# SDP_1.net
KiCad netlist of a schematic drawn in Altium Designer
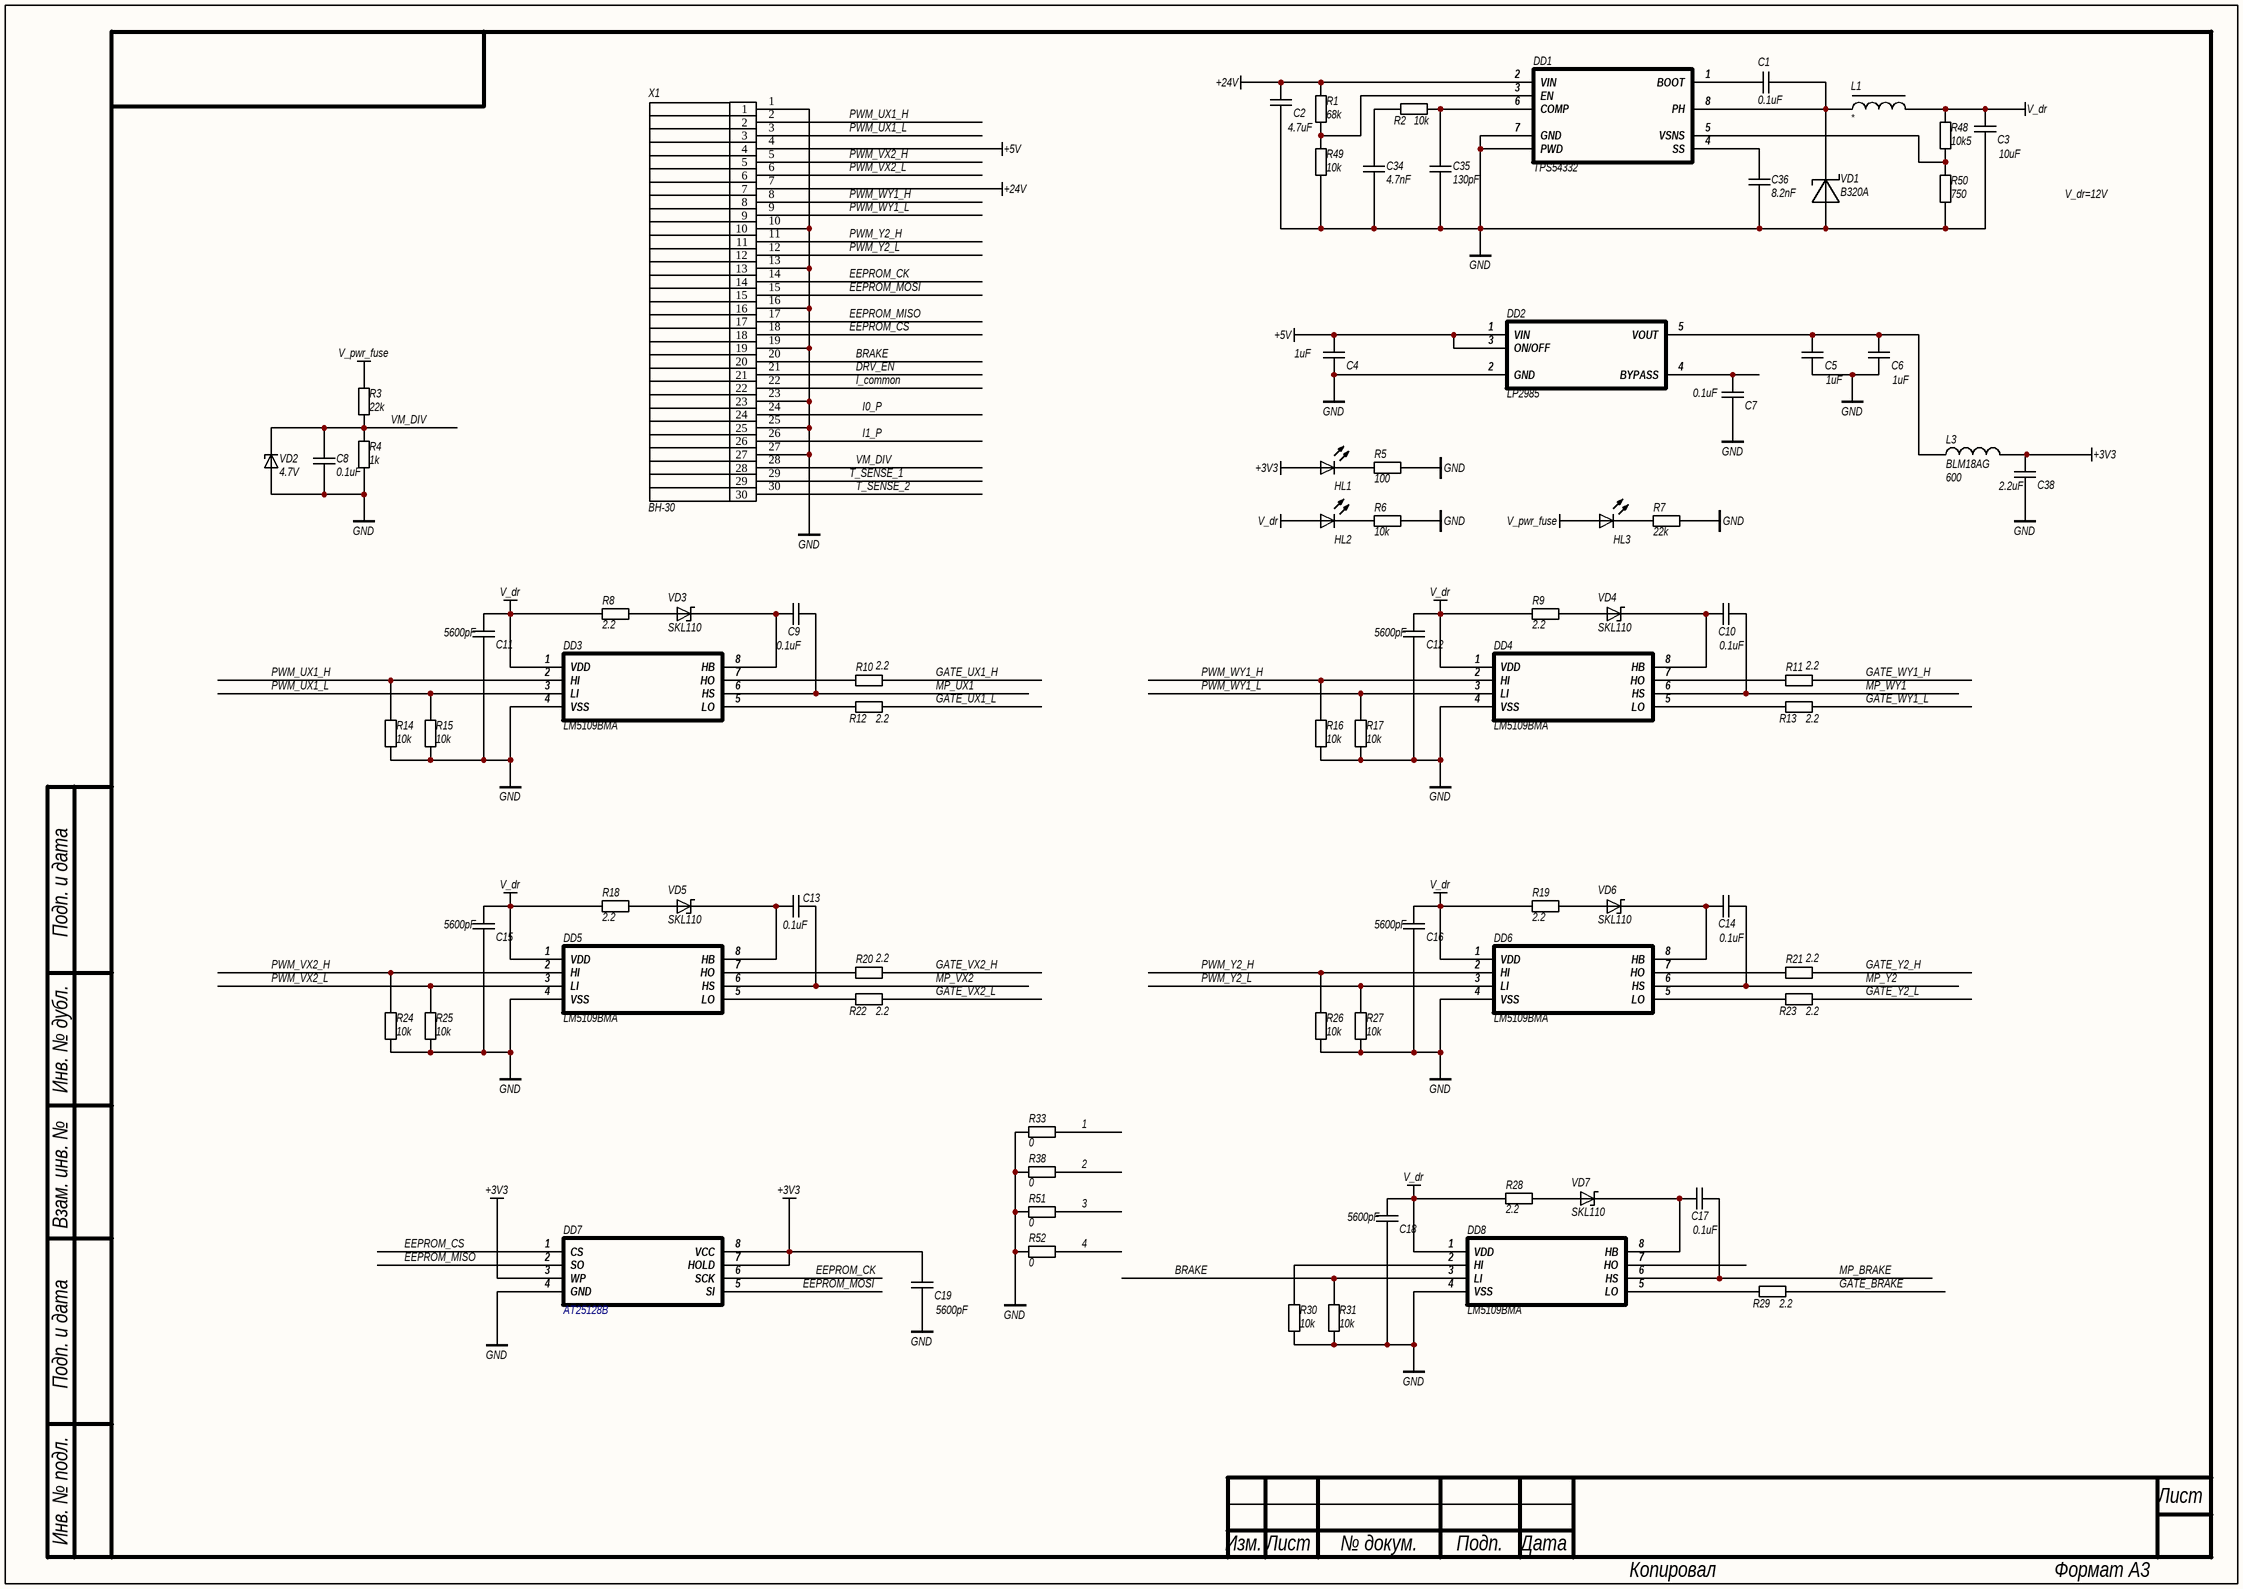
[diagram p0: SDP_1.SchDoc]

(export (version "E")
  (design (tool "Eeschema 10.0.6"))
  (components
    (comp (ref "C1")
      (value "0.1uF")
      (footprint "C0603")
      (description "SMD Capacitor")
      (fields (field (name "MANUFACTURER") "Murata") (field (name "TOLERANCE") "10%"))
      (libsource (lib "VKA") (part "CAP"))
    )
    (comp (ref "C2")
      (value "4.7uF")
      (footprint "C1210")
      (description "SMD Capacitor")
      (fields (field (name "MANUFACTURER") "Murata") (field (name "TOLERANCE") "10%"))
      (libsource (lib "VKA") (part "CAP"))
    )
    (comp (ref "C3")
      (value "10uF")
      (footprint "C1210")
      (description "SMD Capacitor")
      (fields (field (name "MANUFACTURER") "Murata") (field (name "TOLERANCE") "10%"))
      (libsource (lib "VKA") (part "CAP"))
    )
    (comp (ref "C4")
      (value "1uF")
      (footprint "C0603")
      (description "SMD Capacitor")
      (fields (field (name "MANUFACTURER") "Murata") (field (name "TOLERANCE") "10%"))
      (libsource (lib "VKA") (part "CAP"))
    )
    (comp (ref "C5")
      (value "1uF")
      (footprint "C0603")
      (description "SMD Capacitor")
      (fields (field (name "MANUFACTURER") "Murata") (field (name "TOLERANCE") "10%"))
      (libsource (lib "VKA") (part "CAP"))
    )
    (comp (ref "C6")
      (value "1uF")
      (footprint "C0603")
      (description "SMD Capacitor")
      (fields (field (name "MANUFACTURER") "Murata") (field (name "TOLERANCE") "10%"))
      (libsource (lib "VKA") (part "CAP"))
    )
    (comp (ref "C7")
      (value "0.1uF")
      (footprint "C0603")
      (description "SMD Capacitor")
      (fields (field (name "MANUFACTURER") "Murata") (field (name "TOLERANCE") "10%"))
      (libsource (lib "VKA") (part "CAP"))
    )
    (comp (ref "C8")
      (value "0.1uF")
      (footprint "C0603")
      (description "SMD Capacitor")
      (fields (field (name "MANUFACTURER") "Murata") (field (name "TOLERANCE") "10%"))
      (libsource (lib "VKA") (part "CAP"))
    )
    (comp (ref "C9")
      (value "0.1uF")
      (footprint "C0603")
      (description "SMD Capacitor")
      (fields (field (name "MANUFACTURER") "Murata") (field (name "TOLERANCE") "10%"))
      (libsource (lib "VKA") (part "CAP"))
    )
    (comp (ref "C10")
      (value "0.1uF")
      (footprint "C0603")
      (description "SMD Capacitor")
      (fields (field (name "MANUFACTURER") "Murata") (field (name "TOLERANCE") "10%"))
      (libsource (lib "VKA") (part "CAP"))
    )
    (comp (ref "C11")
      (value "5600pF")
      (footprint "C0603")
      (description "SMD Capacitor")
      (fields (field (name "MANUFACTURER") "Murata") (field (name "TOLERANCE") "10%"))
      (libsource (lib "VKA") (part "CAP"))
    )
    (comp (ref "C12")
      (value "5600pF")
      (footprint "C0603")
      (description "SMD Capacitor")
      (fields (field (name "MANUFACTURER") "Murata") (field (name "TOLERANCE") "10%"))
      (libsource (lib "VKA") (part "CAP"))
    )
    (comp (ref "C13")
      (value "0.1uF")
      (footprint "C0603")
      (description "SMD Capacitor")
      (fields (field (name "MANUFACTURER") "Murata") (field (name "TOLERANCE") "10%"))
      (libsource (lib "VKA") (part "CAP"))
    )
    (comp (ref "C14")
      (value "0.1uF")
      (footprint "C0603")
      (description "SMD Capacitor")
      (fields (field (name "MANUFACTURER") "Murata") (field (name "TOLERANCE") "10%"))
      (libsource (lib "VKA") (part "CAP"))
    )
    (comp (ref "C15")
      (value "5600pF")
      (footprint "C0603")
      (description "SMD Capacitor")
      (fields (field (name "MANUFACTURER") "Murata") (field (name "TOLERANCE") "10%"))
      (libsource (lib "VKA") (part "CAP"))
    )
    (comp (ref "C16")
      (value "5600pF")
      (footprint "C0603")
      (description "SMD Capacitor")
      (fields (field (name "MANUFACTURER") "Murata") (field (name "TOLERANCE") "10%"))
      (libsource (lib "VKA") (part "CAP"))
    )
    (comp (ref "C17")
      (value "0.1uF")
      (footprint "C0603")
      (description "SMD Capacitor")
      (fields (field (name "MANUFACTURER") "Murata") (field (name "TOLERANCE") "10%"))
      (libsource (lib "VKA") (part "CAP"))
    )
    (comp (ref "C18")
      (value "5600pF")
      (footprint "C0603")
      (description "SMD Capacitor")
      (fields (field (name "MANUFACTURER") "Murata") (field (name "TOLERANCE") "10%"))
      (libsource (lib "VKA") (part "CAP"))
    )
    (comp (ref "C19")
      (value "5600pF")
      (footprint "C0603")
      (description "SMD Capacitor")
      (fields (field (name "MANUFACTURER") "Murata") (field (name "TOLERANCE") "10%"))
      (libsource (lib "VKA") (part "CAP"))
    )
    (comp (ref "C34")
      (value "4.7nF")
      (footprint "C0603")
      (description "SMD Capacitor")
      (fields (field (name "MANUFACTURER") "Murata") (field (name "TOLERANCE") "10%"))
      (libsource (lib "VKA") (part "CAP"))
    )
    (comp (ref "C35")
      (value "130pF")
      (footprint "C0603")
      (description "SMD Capacitor")
      (fields (field (name "MANUFACTURER") "Murata") (field (name "TOLERANCE") "10%"))
      (libsource (lib "VKA") (part "CAP"))
    )
    (comp (ref "C36")
      (value "8.2nF")
      (footprint "C0603")
      (description "SMD Capacitor")
      (fields (field (name "MANUFACTURER") "Murata") (field (name "TOLERANCE") "10%"))
      (libsource (lib "VKA") (part "CAP"))
    )
    (comp (ref "C38")
      (value "2.2uF")
      (footprint "C0603")
      (description "SMD Capacitor")
      (fields (field (name "MANUFACTURER") "Murata") (field (name "TOLERANCE") "10%"))
      (libsource (lib "VKA") (part "CAP"))
    )
    (comp (ref "DD1") (value "TPS54332") (footprint "DDA") (libsource (lib "VKA") (part "TPS54332")))
    (comp (ref "DD2")
      (value "LP2985")
      (footprint "SOT23-5")
      (description "Regulator")
      (libsource (lib "DSP") (part "LP2985-33DBV"))
    )
    (comp (ref "DD3")
      (value "LM5109BMA")
      (footprint "SO8_L")
      (description "Gate driver")
      (libsource (lib "DSP") (part "LM5109BMA"))
    )
    (comp (ref "DD4")
      (value "LM5109BMA")
      (footprint "SO8_L")
      (description "Gate driver")
      (libsource (lib "DSP") (part "LM5109BMA"))
    )
    (comp (ref "DD5")
      (value "LM5109BMA")
      (footprint "SO8_L")
      (description "Gate driver")
      (libsource (lib "DSP") (part "LM5109BMA"))
    )
    (comp (ref "DD6")
      (value "LM5109BMA")
      (footprint "SO8_L")
      (description "Gate driver")
      (libsource (lib "DSP") (part "LM5109BMA"))
    )
    (comp (ref "DD7")
      (value "AT25128B")
      (footprint "SO8_L")
      (description "EEPROM")
      (libsource (lib "DSP") (part "AT25128B-SSHL"))
    )
    (comp (ref "DD8")
      (value "LM5109BMA")
      (footprint "SO8_L")
      (description "Gate driver")
      (libsource (lib "DSP") (part "LM5109BMA"))
    )
    (comp (ref "HL1") (value "LED0603") (footprint "LED0603") (libsource (lib "VKA") (part "LED0603")))
    (comp (ref "HL2") (value "LED0603") (footprint "LED0603") (libsource (lib "VKA") (part "LED0603")))
    (comp (ref "HL3") (value "LED0603") (footprint "LED0603") (libsource (lib "VKA") (part "LED0603")))
    (comp (ref "L1")
      (value "XAL5050")
      (footprint "XAL5050")
      (description "chip inductor")
      (fields (field (name "ALTIUM_VALUE") "*"))
      (libsource (lib "VKA") (part "XAL5050"))
    )
    (comp (ref "L3")
      (value "BLM18AG")
      (footprint "R0603")
      (fields (field (name "ALTIUM_VALUE") "600"))
      (libsource (lib "VKA") (part "BLM18AG"))
    )
    (comp (ref "R1")
      (value "68k")
      (footprint "R0603")
      (description "SMD Resistor")
      (fields (field (name "POWER") "0.062 Wt") (field (name "TOLERANCE") "5%"))
      (libsource (lib "VKA") (part "RES"))
    )
    (comp (ref "R2")
      (value "10k")
      (footprint "R0603")
      (description "SMD Resistor")
      (fields (field (name "POWER") "0.062 Wt") (field (name "TOLERANCE") "5%"))
      (libsource (lib "") (part "RES_1"))
    )
    (comp (ref "R3")
      (value "22k")
      (footprint "R0603")
      (description "SMD Resistor")
      (fields (field (name "POWER") "0.062 Wt") (field (name "TOLERANCE") "5%"))
      (libsource (lib "VKA") (part "RES"))
    )
    (comp (ref "R4")
      (value "1k")
      (footprint "R0603")
      (description "SMD Resistor")
      (fields (field (name "POWER") "0.062 Wt") (field (name "TOLERANCE") "5%"))
      (libsource (lib "VKA") (part "RES"))
    )
    (comp (ref "R5")
      (value "100")
      (footprint "R0603")
      (description "SMD Resistor")
      (fields (field (name "POWER") "0.062 Wt") (field (name "TOLERANCE") "5%"))
      (libsource (lib "") (part "RES_1"))
    )
    (comp (ref "R6")
      (value "10k")
      (footprint "R0603")
      (description "SMD Resistor")
      (fields (field (name "POWER") "0.062 Wt") (field (name "TOLERANCE") "5%"))
      (libsource (lib "") (part "RES_1"))
    )
    (comp (ref "R7")
      (value "22k")
      (footprint "R0603")
      (description "SMD Resistor")
      (fields (field (name "POWER") "0.062 Wt") (field (name "TOLERANCE") "5%"))
      (libsource (lib "") (part "RES_1"))
    )
    (comp (ref "R8")
      (value "2.2")
      (footprint "R0603")
      (description "SMD Resistor")
      (fields (field (name "POWER") "0.062 Wt") (field (name "TOLERANCE") "5%"))
      (libsource (lib "") (part "RES_2"))
    )
    (comp (ref "R9")
      (value "2.2")
      (footprint "R0603")
      (description "SMD Resistor")
      (fields (field (name "POWER") "0.062 Wt") (field (name "TOLERANCE") "5%"))
      (libsource (lib "") (part "RES_2"))
    )
    (comp (ref "R10")
      (value "2.2")
      (footprint "R0603")
      (description "SMD Resistor")
      (fields (field (name "POWER") "0.062 Wt") (field (name "TOLERANCE") "5%"))
      (libsource (lib "") (part "RES_2"))
    )
    (comp (ref "R11")
      (value "2.2")
      (footprint "R0603")
      (description "SMD Resistor")
      (fields (field (name "POWER") "0.062 Wt") (field (name "TOLERANCE") "5%"))
      (libsource (lib "") (part "RES_2"))
    )
    (comp (ref "R12")
      (value "2.2")
      (footprint "R0603")
      (description "SMD Resistor")
      (fields (field (name "POWER") "0.062 Wt") (field (name "TOLERANCE") "5%"))
      (libsource (lib "") (part "RES_2"))
    )
    (comp (ref "R13")
      (value "2.2")
      (footprint "R0603")
      (description "SMD Resistor")
      (fields (field (name "POWER") "0.062 Wt") (field (name "TOLERANCE") "5%"))
      (libsource (lib "") (part "RES_2"))
    )
    (comp (ref "R14")
      (value "10k")
      (footprint "R0603")
      (description "SMD Resistor")
      (fields (field (name "POWER") "0.062 Wt") (field (name "TOLERANCE") "5%"))
      (libsource (lib "VKA") (part "RES"))
    )
    (comp (ref "R15")
      (value "10k")
      (footprint "R0603")
      (description "SMD Resistor")
      (fields (field (name "POWER") "0.062 Wt") (field (name "TOLERANCE") "5%"))
      (libsource (lib "VKA") (part "RES"))
    )
    (comp (ref "R16")
      (value "10k")
      (footprint "R0603")
      (description "SMD Resistor")
      (fields (field (name "POWER") "0.062 Wt") (field (name "TOLERANCE") "5%"))
      (libsource (lib "VKA") (part "RES"))
    )
    (comp (ref "R17")
      (value "10k")
      (footprint "R0603")
      (description "SMD Resistor")
      (fields (field (name "POWER") "0.062 Wt") (field (name "TOLERANCE") "5%"))
      (libsource (lib "VKA") (part "RES"))
    )
    (comp (ref "R18")
      (value "2.2")
      (footprint "R0603")
      (description "SMD Resistor")
      (fields (field (name "POWER") "0.062 Wt") (field (name "TOLERANCE") "5%"))
      (libsource (lib "") (part "RES_2"))
    )
    (comp (ref "R19")
      (value "2.2")
      (footprint "R0603")
      (description "SMD Resistor")
      (fields (field (name "POWER") "0.062 Wt") (field (name "TOLERANCE") "5%"))
      (libsource (lib "") (part "RES_2"))
    )
    (comp (ref "R20")
      (value "2.2")
      (footprint "R0603")
      (description "SMD Resistor")
      (fields (field (name "POWER") "0.062 Wt") (field (name "TOLERANCE") "5%"))
      (libsource (lib "") (part "RES_2"))
    )
    (comp (ref "R21")
      (value "2.2")
      (footprint "R0603")
      (description "SMD Resistor")
      (fields (field (name "POWER") "0.062 Wt") (field (name "TOLERANCE") "5%"))
      (libsource (lib "") (part "RES_2"))
    )
    (comp (ref "R22")
      (value "2.2")
      (footprint "R0603")
      (description "SMD Resistor")
      (fields (field (name "POWER") "0.062 Wt") (field (name "TOLERANCE") "5%"))
      (libsource (lib "") (part "RES_2"))
    )
    (comp (ref "R23")
      (value "2.2")
      (footprint "R0603")
      (description "SMD Resistor")
      (fields (field (name "POWER") "0.062 Wt") (field (name "TOLERANCE") "5%"))
      (libsource (lib "") (part "RES_2"))
    )
    (comp (ref "R24")
      (value "10k")
      (footprint "R0603")
      (description "SMD Resistor")
      (fields (field (name "POWER") "0.062 Wt") (field (name "TOLERANCE") "5%"))
      (libsource (lib "VKA") (part "RES"))
    )
    (comp (ref "R25")
      (value "10k")
      (footprint "R0603")
      (description "SMD Resistor")
      (fields (field (name "POWER") "0.062 Wt") (field (name "TOLERANCE") "5%"))
      (libsource (lib "VKA") (part "RES"))
    )
    (comp (ref "R26")
      (value "10k")
      (footprint "R0603")
      (description "SMD Resistor")
      (fields (field (name "POWER") "0.062 Wt") (field (name "TOLERANCE") "5%"))
      (libsource (lib "VKA") (part "RES"))
    )
    (comp (ref "R27")
      (value "10k")
      (footprint "R0603")
      (description "SMD Resistor")
      (fields (field (name "POWER") "0.062 Wt") (field (name "TOLERANCE") "5%"))
      (libsource (lib "VKA") (part "RES"))
    )
    (comp (ref "R28")
      (value "2.2")
      (footprint "R0603")
      (description "SMD Resistor")
      (fields (field (name "POWER") "0.062 Wt") (field (name "TOLERANCE") "5%"))
      (libsource (lib "") (part "RES_2"))
    )
    (comp (ref "R29")
      (value "2.2")
      (footprint "R0603")
      (description "SMD Resistor")
      (fields (field (name "POWER") "0.062 Wt") (field (name "TOLERANCE") "5%"))
      (libsource (lib "") (part "RES_2"))
    )
    (comp (ref "R30")
      (value "10k")
      (footprint "R0603")
      (description "SMD Resistor")
      (fields (field (name "POWER") "0.062 Wt") (field (name "TOLERANCE") "5%"))
      (libsource (lib "VKA") (part "RES"))
    )
    (comp (ref "R31")
      (value "10k")
      (footprint "R0603")
      (description "SMD Resistor")
      (fields (field (name "POWER") "0.062 Wt") (field (name "TOLERANCE") "5%"))
      (libsource (lib "VKA") (part "RES"))
    )
    (comp (ref "R33")
      (value "0")
      (footprint "R0603")
      (description "SMD Resistor")
      (fields (field (name "POWER") "0.062 Wt") (field (name "TOLERANCE") "5%"))
      (libsource (lib "") (part "RES_1"))
    )
    (comp (ref "R38")
      (value "0")
      (footprint "R0603")
      (description "SMD Resistor")
      (fields (field (name "POWER") "0.062 Wt") (field (name "TOLERANCE") "5%"))
      (libsource (lib "") (part "RES_1"))
    )
    (comp (ref "R48")
      (value "10k5")
      (footprint "R0603")
      (description "SMD Resistor")
      (fields (field (name "POWER") "0.062 Wt") (field (name "TOLERANCE") "5%"))
      (libsource (lib "VKA") (part "RES"))
    )
    (comp (ref "R49")
      (value "10k")
      (footprint "R0603")
      (description "SMD Resistor")
      (fields (field (name "POWER") "0.062 Wt") (field (name "TOLERANCE") "5%"))
      (libsource (lib "VKA") (part "RES"))
    )
    (comp (ref "R50")
      (value "750")
      (footprint "R0603")
      (description "SMD Resistor")
      (fields (field (name "POWER") "0.062 Wt") (field (name "TOLERANCE") "5%"))
      (libsource (lib "VKA") (part "RES"))
    )
    (comp (ref "R51")
      (value "0")
      (footprint "R0603")
      (description "SMD Resistor")
      (fields (field (name "POWER") "0.062 Wt") (field (name "TOLERANCE") "5%"))
      (libsource (lib "") (part "RES_1"))
    )
    (comp (ref "R52")
      (value "0")
      (footprint "R0603")
      (description "SMD Resistor")
      (fields (field (name "POWER") "0.062 Wt") (field (name "TOLERANCE") "5%"))
      (libsource (lib "") (part "RES_1"))
    )
    (comp (ref "VD1")
      (value "B320A")
      (footprint "SMA-DO214")
      (description "Shottky diode")
      (libsource (lib "VKA") (part "B320A"))
    )
    (comp (ref "VD2")
      (value "BZX384")
      (footprint "SOD323")
      (fields (field (name "VOLTAGE") "4.7V"))
      (libsource (lib "VKA") (part "BZX384"))
    )
    (comp (ref "VD3")
      (value "SKL110")
      (footprint "SOD-123")
      (description "Shottky rectifier")
      (libsource (lib "DSP") (part "SKL110"))
    )
    (comp (ref "VD4")
      (value "SKL110")
      (footprint "SOD-123")
      (description "Shottky rectifier")
      (libsource (lib "DSP") (part "SKL110"))
    )
    (comp (ref "VD5")
      (value "SKL110")
      (footprint "SOD-123")
      (description "Shottky rectifier")
      (libsource (lib "DSP") (part "SKL110"))
    )
    (comp (ref "VD6")
      (value "SKL110")
      (footprint "SOD-123")
      (description "Shottky rectifier")
      (libsource (lib "DSP") (part "SKL110"))
    )
    (comp (ref "VD7")
      (value "SKL110")
      (footprint "SOD-123")
      (description "Shottky rectifier")
      (libsource (lib "DSP") (part "SKL110"))
    )
    (comp (ref "X1")
      (value "BH-30")
      (footprint "IDC-30(BH-30)")
      (libsource (lib "VKA") (part "IDC15x2_GOST"))
    )
  )
  (nets
    (net (code "1") (name "+3V3") (class "Default")
      (node (ref "C19") (pin "2") (pinfunction "2_2") (pintype "passive"))
      (node (ref "C38") (pin "2") (pinfunction "2_2") (pintype "passive"))
      (node (ref "DD7") (pin "3") (pinfunction "WP_3") (pintype "passive"))
      (node (ref "DD7") (pin "7") (pinfunction "HOLD_7") (pintype "passive"))
      (node (ref "DD7") (pin "8") (pinfunction "VCC_8") (pintype "passive"))
      (node (ref "HL1") (pin "1") (pinfunction "A_1") (pintype "passive"))
      (node (ref "L3") (pin "2") (pinfunction "2_2") (pintype "passive"))
    )
    (net (code "2") (name "+5V") (class "Default")
      (node (ref "C4") (pin "2") (pinfunction "2_2") (pintype "passive"))
      (node (ref "DD2") (pin "1") (pinfunction "VIN_1") (pintype "passive"))
      (node (ref "DD2") (pin "3") (pinfunction "ON/OFF_3") (pintype "passive"))
      (node (ref "X1") (pin "4") (pinfunction "4_4") (pintype "passive"))
    )
    (net (code "3") (name "+24V") (class "Default")
      (node (ref "C2") (pin "2") (pinfunction "2_2") (pintype "passive"))
      (node (ref "DD1") (pin "2") (pinfunction "VIN_2") (pintype "passive"))
      (node (ref "R1") (pin "2") (pinfunction "2_2") (pintype "passive"))
      (node (ref "X1") (pin "7") (pinfunction "7_7") (pintype "passive"))
    )
    (net (code "4") (name "/1") (class "Default")
      (node (ref "R33") (pin "1") (pinfunction "1_1") (pintype "passive"))
    )
    (net (code "5") (name "/2") (class "Default")
      (node (ref "R38") (pin "1") (pinfunction "1_1") (pintype "passive"))
    )
    (net (code "6") (name "/3") (class "Default")
      (node (ref "R51") (pin "1") (pinfunction "1_1") (pintype "passive"))
    )
    (net (code "7") (name "/4") (class "Default")
      (node (ref "R52") (pin "1") (pinfunction "1_1") (pintype "passive"))
    )
    (net (code "8") (name "/BRAKE") (class "Default")
      (node (ref "DD8") (pin "3") (pinfunction "LI_3") (pintype "passive"))
      (node (ref "R31") (pin "2") (pinfunction "2_2") (pintype "passive"))
      (node (ref "X1") (pin "20") (pinfunction "20_20") (pintype "passive"))
    )
    (net (code "9") (name "/DRV_EN") (class "Default")
      (node (ref "X1") (pin "21") (pinfunction "21_21") (pintype "passive"))
    )
    (net (code "10") (name "/EEPROM_CK") (class "Default")
      (node (ref "DD7") (pin "6") (pinfunction "SCK_6") (pintype "passive"))
      (node (ref "X1") (pin "14") (pinfunction "14_14") (pintype "passive"))
    )
    (net (code "11") (name "/EEPROM_CS") (class "Default")
      (node (ref "DD7") (pin "1") (pinfunction "CS_1") (pintype "passive"))
      (node (ref "X1") (pin "18") (pinfunction "18_18") (pintype "passive"))
    )
    (net (code "12") (name "/EEPROM_MISO") (class "Default")
      (node (ref "DD7") (pin "2") (pinfunction "SO_2") (pintype "passive"))
      (node (ref "X1") (pin "17") (pinfunction "17_17") (pintype "passive"))
    )
    (net (code "13") (name "/EEPROM_MOSI") (class "Default")
      (node (ref "DD7") (pin "5") (pinfunction "SI_5") (pintype "passive"))
      (node (ref "X1") (pin "15") (pinfunction "15_15") (pintype "passive"))
    )
    (net (code "14") (name "/GATE_BRAKE") (class "Default")
      (node (ref "R29") (pin "2") (pinfunction "2_2") (pintype "passive"))
    )
    (net (code "15") (name "/GATE_UX1_H") (class "Default")
      (node (ref "R10") (pin "2") (pinfunction "2_2") (pintype "passive"))
    )
    (net (code "16") (name "/GATE_UX1_L") (class "Default")
      (node (ref "R12") (pin "2") (pinfunction "2_2") (pintype "passive"))
    )
    (net (code "17") (name "/GATE_VX2_H") (class "Default")
      (node (ref "R20") (pin "2") (pinfunction "2_2") (pintype "passive"))
    )
    (net (code "18") (name "/GATE_VX2_L") (class "Default")
      (node (ref "R22") (pin "2") (pinfunction "2_2") (pintype "passive"))
    )
    (net (code "19") (name "/GATE_WY1_H") (class "Default")
      (node (ref "R11") (pin "2") (pinfunction "2_2") (pintype "passive"))
    )
    (net (code "20") (name "/GATE_WY1_L") (class "Default")
      (node (ref "R13") (pin "2") (pinfunction "2_2") (pintype "passive"))
    )
    (net (code "21") (name "/GATE_Y2_H") (class "Default")
      (node (ref "R21") (pin "2") (pinfunction "2_2") (pintype "passive"))
    )
    (net (code "22") (name "/GATE_Y2_L") (class "Default")
      (node (ref "R23") (pin "2") (pinfunction "2_2") (pintype "passive"))
    )
    (net (code "23") (name "/I0_P") (class "Default")
      (node (ref "X1") (pin "24") (pinfunction "24_24") (pintype "passive"))
    )
    (net (code "24") (name "/I1_P") (class "Default")
      (node (ref "X1") (pin "26") (pinfunction "26_26") (pintype "passive"))
    )
    (net (code "25") (name "/I_common") (class "Default")
      (node (ref "X1") (pin "22") (pinfunction "22_22") (pintype "passive"))
    )
    (net (code "26") (name "/MP_BRAKE") (class "Default")
      (node (ref "C17") (pin "2") (pinfunction "2_2") (pintype "passive"))
      (node (ref "DD8") (pin "6") (pinfunction "HS_6") (pintype "passive"))
    )
    (net (code "27") (name "/MP_UX1") (class "Default")
      (node (ref "C9") (pin "2") (pinfunction "2_2") (pintype "passive"))
      (node (ref "DD3") (pin "6") (pinfunction "HS_6") (pintype "passive"))
    )
    (net (code "28") (name "/MP_VX2") (class "Default")
      (node (ref "C13") (pin "2") (pinfunction "2_2") (pintype "passive"))
      (node (ref "DD5") (pin "6") (pinfunction "HS_6") (pintype "passive"))
    )
    (net (code "29") (name "/MP_WY1") (class "Default")
      (node (ref "C10") (pin "2") (pinfunction "2_2") (pintype "passive"))
      (node (ref "DD4") (pin "6") (pinfunction "HS_6") (pintype "passive"))
    )
    (net (code "30") (name "/MP_Y2") (class "Default")
      (node (ref "C14") (pin "2") (pinfunction "2_2") (pintype "passive"))
      (node (ref "DD6") (pin "6") (pinfunction "HS_6") (pintype "passive"))
    )
    (net (code "31") (name "/PWM_UX1_H") (class "Default")
      (node (ref "DD3") (pin "2") (pinfunction "HI_2") (pintype "passive"))
      (node (ref "R14") (pin "2") (pinfunction "2_2") (pintype "passive"))
      (node (ref "X1") (pin "2") (pinfunction "2_2") (pintype "passive"))
    )
    (net (code "32") (name "/PWM_UX1_L") (class "Default")
      (node (ref "DD3") (pin "3") (pinfunction "LI_3") (pintype "passive"))
      (node (ref "R15") (pin "2") (pinfunction "2_2") (pintype "passive"))
      (node (ref "X1") (pin "3") (pinfunction "3_3") (pintype "passive"))
    )
    (net (code "33") (name "/PWM_VX2_H") (class "Default")
      (node (ref "DD5") (pin "2") (pinfunction "HI_2") (pintype "passive"))
      (node (ref "R24") (pin "2") (pinfunction "2_2") (pintype "passive"))
      (node (ref "X1") (pin "5") (pinfunction "5_5") (pintype "passive"))
    )
    (net (code "34") (name "/PWM_VX2_L") (class "Default")
      (node (ref "DD5") (pin "3") (pinfunction "LI_3") (pintype "passive"))
      (node (ref "R25") (pin "2") (pinfunction "2_2") (pintype "passive"))
      (node (ref "X1") (pin "6") (pinfunction "6_6") (pintype "passive"))
    )
    (net (code "35") (name "/PWM_WY1_H") (class "Default")
      (node (ref "DD4") (pin "2") (pinfunction "HI_2") (pintype "passive"))
      (node (ref "R16") (pin "2") (pinfunction "2_2") (pintype "passive"))
      (node (ref "X1") (pin "8") (pinfunction "8_8") (pintype "passive"))
    )
    (net (code "36") (name "/PWM_WY1_L") (class "Default")
      (node (ref "DD4") (pin "3") (pinfunction "LI_3") (pintype "passive"))
      (node (ref "R17") (pin "2") (pinfunction "2_2") (pintype "passive"))
      (node (ref "X1") (pin "9") (pinfunction "9_9") (pintype "passive"))
    )
    (net (code "37") (name "/PWM_Y2_H") (class "Default")
      (node (ref "DD6") (pin "2") (pinfunction "HI_2") (pintype "passive"))
      (node (ref "R26") (pin "2") (pinfunction "2_2") (pintype "passive"))
      (node (ref "X1") (pin "11") (pinfunction "11_11") (pintype "passive"))
    )
    (net (code "38") (name "/PWM_Y2_L") (class "Default")
      (node (ref "DD6") (pin "3") (pinfunction "LI_3") (pintype "passive"))
      (node (ref "R27") (pin "2") (pinfunction "2_2") (pintype "passive"))
      (node (ref "X1") (pin "12") (pinfunction "12_12") (pintype "passive"))
    )
    (net (code "39") (name "/T_SENSE_1") (class "Default")
      (node (ref "X1") (pin "29") (pinfunction "29_29") (pintype "passive"))
    )
    (net (code "40") (name "/T_SENSE_2") (class "Default")
      (node (ref "X1") (pin "30") (pinfunction "30_30") (pintype "passive"))
    )
    (net (code "41") (name "/VM_DIV") (class "Default")
      (node (ref "C8") (pin "2") (pinfunction "2_2") (pintype "passive"))
      (node (ref "R3") (pin "1") (pinfunction "1_1") (pintype "passive"))
      (node (ref "R4") (pin "2") (pinfunction "2_2") (pintype "passive"))
      (node (ref "VD2") (pin "2") (pinfunction "K_2") (pintype "passive"))
      (node (ref "X1") (pin "28") (pinfunction "28_28") (pintype "passive"))
    )
    (net (code "42") (name "GND") (class "Default")
      (node (ref "C11") (pin "1") (pinfunction "1_1") (pintype "passive"))
      (node (ref "C12") (pin "1") (pinfunction "1_1") (pintype "passive"))
      (node (ref "C15") (pin "1") (pinfunction "1_1") (pintype "passive"))
      (node (ref "C16") (pin "1") (pinfunction "1_1") (pintype "passive"))
      (node (ref "C18") (pin "1") (pinfunction "1_1") (pintype "passive"))
      (node (ref "C19") (pin "1") (pinfunction "1_1") (pintype "passive"))
      (node (ref "C2") (pin "1") (pinfunction "1_1") (pintype "passive"))
      (node (ref "C3") (pin "1") (pinfunction "1_1") (pintype "passive"))
      (node (ref "C34") (pin "1") (pinfunction "1_1") (pintype "passive"))
      (node (ref "C35") (pin "1") (pinfunction "1_1") (pintype "passive"))
      (node (ref "C36") (pin "1") (pinfunction "1_1") (pintype "passive"))
      (node (ref "C38") (pin "1") (pinfunction "1_1") (pintype "passive"))
      (node (ref "C4") (pin "1") (pinfunction "1_1") (pintype "passive"))
      (node (ref "C5") (pin "1") (pinfunction "1_1") (pintype "passive"))
      (node (ref "C6") (pin "1") (pinfunction "1_1") (pintype "passive"))
      (node (ref "C7") (pin "1") (pinfunction "1_1") (pintype "passive"))
      (node (ref "C8") (pin "1") (pinfunction "1_1") (pintype "passive"))
      (node (ref "DD1") (pin "7") (pinfunction "GND_7") (pintype "passive"))
      (node (ref "DD1") (pin "9") (pinfunction "PWD_9") (pintype "passive"))
      (node (ref "DD2") (pin "2") (pinfunction "GND_2") (pintype "passive"))
      (node (ref "DD3") (pin "4") (pinfunction "VSS_4") (pintype "passive"))
      (node (ref "DD4") (pin "4") (pinfunction "VSS_4") (pintype "passive"))
      (node (ref "DD5") (pin "4") (pinfunction "VSS_4") (pintype "passive"))
      (node (ref "DD6") (pin "4") (pinfunction "VSS_4") (pintype "passive"))
      (node (ref "DD7") (pin "4") (pinfunction "GND_4") (pintype "passive"))
      (node (ref "DD8") (pin "4") (pinfunction "VSS_4") (pintype "passive"))
      (node (ref "R14") (pin "1") (pinfunction "1_1") (pintype "passive"))
      (node (ref "R15") (pin "1") (pinfunction "1_1") (pintype "passive"))
      (node (ref "R16") (pin "1") (pinfunction "1_1") (pintype "passive"))
      (node (ref "R17") (pin "1") (pinfunction "1_1") (pintype "passive"))
      (node (ref "R24") (pin "1") (pinfunction "1_1") (pintype "passive"))
      (node (ref "R25") (pin "1") (pinfunction "1_1") (pintype "passive"))
      (node (ref "R26") (pin "1") (pinfunction "1_1") (pintype "passive"))
      (node (ref "R27") (pin "1") (pinfunction "1_1") (pintype "passive"))
      (node (ref "R30") (pin "1") (pinfunction "1_1") (pintype "passive"))
      (node (ref "R31") (pin "1") (pinfunction "1_1") (pintype "passive"))
      (node (ref "R33") (pin "2") (pinfunction "2_2") (pintype "passive"))
      (node (ref "R38") (pin "2") (pinfunction "2_2") (pintype "passive"))
      (node (ref "R4") (pin "1") (pinfunction "1_1") (pintype "passive"))
      (node (ref "R49") (pin "1") (pinfunction "1_1") (pintype "passive"))
      (node (ref "R5") (pin "1") (pinfunction "1_1") (pintype "passive"))
      (node (ref "R50") (pin "1") (pinfunction "1_1") (pintype "passive"))
      (node (ref "R51") (pin "2") (pinfunction "2_2") (pintype "passive"))
      (node (ref "R52") (pin "2") (pinfunction "2_2") (pintype "passive"))
      (node (ref "R6") (pin "1") (pinfunction "1_1") (pintype "passive"))
      (node (ref "R7") (pin "1") (pinfunction "1_1") (pintype "passive"))
      (node (ref "VD1") (pin "1") (pinfunction "A_1") (pintype "passive"))
      (node (ref "VD2") (pin "1") (pinfunction "A_1") (pintype "passive"))
      (node (ref "X1") (pin "1") (pinfunction "1_1") (pintype "passive"))
      (node (ref "X1") (pin "10") (pinfunction "10_10") (pintype "passive"))
      (node (ref "X1") (pin "13") (pinfunction "13_13") (pintype "passive"))
      (node (ref "X1") (pin "16") (pinfunction "16_16") (pintype "passive"))
      (node (ref "X1") (pin "19") (pinfunction "19_19") (pintype "passive"))
      (node (ref "X1") (pin "23") (pinfunction "23_23") (pintype "passive"))
      (node (ref "X1") (pin "25") (pinfunction "25_25") (pintype "passive"))
      (node (ref "X1") (pin "27") (pinfunction "27_27") (pintype "passive"))
    )
    (net (code "43") (name "Net-(C34-Pad2)") (class "Default")
      (node (ref "C34") (pin "2") (pinfunction "2_2") (pintype "passive"))
      (node (ref "R2") (pin "2") (pinfunction "2_2") (pintype "passive"))
    )
    (net (code "44") (name "Net-(DD1-BOOT)") (class "Default")
      (node (ref "C1") (pin "2") (pinfunction "2_2") (pintype "passive"))
      (node (ref "DD1") (pin "1") (pinfunction "BOOT_1") (pintype "passive"))
    )
    (net (code "45") (name "Net-(DD1-COMP)") (class "Default")
      (node (ref "C35") (pin "2") (pinfunction "2_2") (pintype "passive"))
      (node (ref "DD1") (pin "6") (pinfunction "COMP_6") (pintype "passive"))
      (node (ref "R2") (pin "1") (pinfunction "1_1") (pintype "passive"))
    )
    (net (code "46") (name "Net-(DD1-EN)") (class "Default")
      (node (ref "DD1") (pin "3") (pinfunction "EN_3") (pintype "passive"))
      (node (ref "R1") (pin "1") (pinfunction "1_1") (pintype "passive"))
      (node (ref "R49") (pin "2") (pinfunction "2_2") (pintype "passive"))
    )
    (net (code "47") (name "Net-(DD1-PH)") (class "Default")
      (node (ref "C1") (pin "1") (pinfunction "1_1") (pintype "passive"))
      (node (ref "DD1") (pin "8") (pinfunction "PH_8") (pintype "passive"))
      (node (ref "L1") (pin "1") (pinfunction "1_1") (pintype "passive"))
      (node (ref "VD1") (pin "2") (pinfunction "K_2") (pintype "passive"))
    )
    (net (code "48") (name "Net-(DD1-SS)") (class "Default")
      (node (ref "C36") (pin "2") (pinfunction "2_2") (pintype "passive"))
      (node (ref "DD1") (pin "4") (pinfunction "SS_4") (pintype "passive"))
    )
    (net (code "49") (name "Net-(DD1-VSNS)") (class "Default")
      (node (ref "DD1") (pin "5") (pinfunction "VSNS_5") (pintype "passive"))
      (node (ref "R48") (pin "1") (pinfunction "1_1") (pintype "passive"))
      (node (ref "R50") (pin "2") (pinfunction "2_2") (pintype "passive"))
    )
    (net (code "50") (name "Net-(DD2-BYPASS)") (class "Default")
      (node (ref "C7") (pin "2") (pinfunction "2_2") (pintype "passive"))
      (node (ref "DD2") (pin "4") (pinfunction "BYPASS_4") (pintype "passive"))
    )
    (net (code "51") (name "Net-(DD2-VOUT)") (class "Default")
      (node (ref "C5") (pin "2") (pinfunction "2_2") (pintype "passive"))
      (node (ref "C6") (pin "2") (pinfunction "2_2") (pintype "passive"))
      (node (ref "DD2") (pin "5") (pinfunction "VOUT_5") (pintype "passive"))
      (node (ref "L3") (pin "1") (pinfunction "1_1") (pintype "passive"))
    )
    (net (code "52") (name "Net-(DD3-HB)") (class "Default")
      (node (ref "C9") (pin "1") (pinfunction "1_1") (pintype "passive"))
      (node (ref "DD3") (pin "8") (pinfunction "HB_8") (pintype "passive"))
      (node (ref "VD3") (pin "2") (pinfunction "K_2") (pintype "passive"))
    )
    (net (code "53") (name "Net-(DD3-HO)") (class "Default")
      (node (ref "DD3") (pin "7") (pinfunction "HO_7") (pintype "passive"))
      (node (ref "R10") (pin "1") (pinfunction "1_1") (pintype "passive"))
    )
    (net (code "54") (name "Net-(DD3-LO)") (class "Default")
      (node (ref "DD3") (pin "5") (pinfunction "LO_5") (pintype "passive"))
      (node (ref "R12") (pin "1") (pinfunction "1_1") (pintype "passive"))
    )
    (net (code "55") (name "Net-(DD4-HB)") (class "Default")
      (node (ref "C10") (pin "1") (pinfunction "1_1") (pintype "passive"))
      (node (ref "DD4") (pin "8") (pinfunction "HB_8") (pintype "passive"))
      (node (ref "VD4") (pin "2") (pinfunction "K_2") (pintype "passive"))
    )
    (net (code "56") (name "Net-(DD4-HO)") (class "Default")
      (node (ref "DD4") (pin "7") (pinfunction "HO_7") (pintype "passive"))
      (node (ref "R11") (pin "1") (pinfunction "1_1") (pintype "passive"))
    )
    (net (code "57") (name "Net-(DD4-LO)") (class "Default")
      (node (ref "DD4") (pin "5") (pinfunction "LO_5") (pintype "passive"))
      (node (ref "R13") (pin "1") (pinfunction "1_1") (pintype "passive"))
    )
    (net (code "58") (name "Net-(DD5-HB)") (class "Default")
      (node (ref "C13") (pin "1") (pinfunction "1_1") (pintype "passive"))
      (node (ref "DD5") (pin "8") (pinfunction "HB_8") (pintype "passive"))
      (node (ref "VD5") (pin "2") (pinfunction "K_2") (pintype "passive"))
    )
    (net (code "59") (name "Net-(DD5-HO)") (class "Default")
      (node (ref "DD5") (pin "7") (pinfunction "HO_7") (pintype "passive"))
      (node (ref "R20") (pin "1") (pinfunction "1_1") (pintype "passive"))
    )
    (net (code "60") (name "Net-(DD5-LO)") (class "Default")
      (node (ref "DD5") (pin "5") (pinfunction "LO_5") (pintype "passive"))
      (node (ref "R22") (pin "1") (pinfunction "1_1") (pintype "passive"))
    )
    (net (code "61") (name "Net-(DD6-HB)") (class "Default")
      (node (ref "C14") (pin "1") (pinfunction "1_1") (pintype "passive"))
      (node (ref "DD6") (pin "8") (pinfunction "HB_8") (pintype "passive"))
      (node (ref "VD6") (pin "2") (pinfunction "K_2") (pintype "passive"))
    )
    (net (code "62") (name "Net-(DD6-HO)") (class "Default")
      (node (ref "DD6") (pin "7") (pinfunction "HO_7") (pintype "passive"))
      (node (ref "R21") (pin "1") (pinfunction "1_1") (pintype "passive"))
    )
    (net (code "63") (name "Net-(DD6-LO)") (class "Default")
      (node (ref "DD6") (pin "5") (pinfunction "LO_5") (pintype "passive"))
      (node (ref "R23") (pin "1") (pinfunction "1_1") (pintype "passive"))
    )
    (net (code "64") (name "Net-(DD8-HB)") (class "Default")
      (node (ref "C17") (pin "1") (pinfunction "1_1") (pintype "passive"))
      (node (ref "DD8") (pin "8") (pinfunction "HB_8") (pintype "passive"))
      (node (ref "VD7") (pin "2") (pinfunction "K_2") (pintype "passive"))
    )
    (net (code "65") (name "Net-(DD8-HI)") (class "Default")
      (node (ref "DD8") (pin "2") (pinfunction "HI_2") (pintype "passive"))
      (node (ref "R30") (pin "2") (pinfunction "2_2") (pintype "passive"))
    )
    (net (code "66") (name "Net-(DD8-LO)") (class "Default")
      (node (ref "DD8") (pin "5") (pinfunction "LO_5") (pintype "passive"))
      (node (ref "R29") (pin "1") (pinfunction "1_1") (pintype "passive"))
    )
    (net (code "67") (name "Net-(HL1-K)") (class "Default")
      (node (ref "HL1") (pin "2") (pinfunction "K_2") (pintype "passive"))
      (node (ref "R5") (pin "2") (pinfunction "2_2") (pintype "passive"))
    )
    (net (code "68") (name "Net-(HL2-K)") (class "Default")
      (node (ref "HL2") (pin "2") (pinfunction "K_2") (pintype "passive"))
      (node (ref "R6") (pin "2") (pinfunction "2_2") (pintype "passive"))
    )
    (net (code "69") (name "Net-(HL3-K)") (class "Default")
      (node (ref "HL3") (pin "2") (pinfunction "K_2") (pintype "passive"))
      (node (ref "R7") (pin "2") (pinfunction "2_2") (pintype "passive"))
    )
    (net (code "70") (name "Net-(VD3-A)") (class "Default")
      (node (ref "R8") (pin "2") (pinfunction "2_2") (pintype "passive"))
      (node (ref "VD3") (pin "1") (pinfunction "A_1") (pintype "passive"))
    )
    (net (code "71") (name "Net-(VD4-A)") (class "Default")
      (node (ref "R9") (pin "2") (pinfunction "2_2") (pintype "passive"))
      (node (ref "VD4") (pin "1") (pinfunction "A_1") (pintype "passive"))
    )
    (net (code "72") (name "Net-(VD5-A)") (class "Default")
      (node (ref "R18") (pin "2") (pinfunction "2_2") (pintype "passive"))
      (node (ref "VD5") (pin "1") (pinfunction "A_1") (pintype "passive"))
    )
    (net (code "73") (name "Net-(VD6-A)") (class "Default")
      (node (ref "R19") (pin "2") (pinfunction "2_2") (pintype "passive"))
      (node (ref "VD6") (pin "1") (pinfunction "A_1") (pintype "passive"))
    )
    (net (code "74") (name "Net-(VD7-A)") (class "Default")
      (node (ref "R28") (pin "2") (pinfunction "2_2") (pintype "passive"))
      (node (ref "VD7") (pin "1") (pinfunction "A_1") (pintype "passive"))
    )
    (net (code "75") (name "V_dr") (class "Default")
      (node (ref "C11") (pin "2") (pinfunction "2_2") (pintype "passive"))
      (node (ref "C12") (pin "2") (pinfunction "2_2") (pintype "passive"))
      (node (ref "C15") (pin "2") (pinfunction "2_2") (pintype "passive"))
      (node (ref "C16") (pin "2") (pinfunction "2_2") (pintype "passive"))
      (node (ref "C18") (pin "2") (pinfunction "2_2") (pintype "passive"))
      (node (ref "C3") (pin "2") (pinfunction "2_2") (pintype "passive"))
      (node (ref "DD3") (pin "1") (pinfunction "VDD_1") (pintype "passive"))
      (node (ref "DD4") (pin "1") (pinfunction "VDD_1") (pintype "passive"))
      (node (ref "DD5") (pin "1") (pinfunction "VDD_1") (pintype "passive"))
      (node (ref "DD6") (pin "1") (pinfunction "VDD_1") (pintype "passive"))
      (node (ref "DD8") (pin "1") (pinfunction "VDD_1") (pintype "passive"))
      (node (ref "HL2") (pin "1") (pinfunction "A_1") (pintype "passive"))
      (node (ref "L1") (pin "2") (pinfunction "2_2") (pintype "passive"))
      (node (ref "R18") (pin "1") (pinfunction "1_1") (pintype "passive"))
      (node (ref "R19") (pin "1") (pinfunction "1_1") (pintype "passive"))
      (node (ref "R28") (pin "1") (pinfunction "1_1") (pintype "passive"))
      (node (ref "R48") (pin "2") (pinfunction "2_2") (pintype "passive"))
      (node (ref "R8") (pin "1") (pinfunction "1_1") (pintype "passive"))
      (node (ref "R9") (pin "1") (pinfunction "1_1") (pintype "passive"))
    )
    (net (code "76") (name "V_pwr_fuse") (class "Default")
      (node (ref "HL3") (pin "1") (pinfunction "A_1") (pintype "passive"))
      (node (ref "R3") (pin "2") (pinfunction "2_2") (pintype "passive"))
    )
    (net (code "77") (name "unconnected-(DD8-HO-Pad7)") (class "Default")
      (node (ref "DD8") (pin "7") (pinfunction "HO_7") (pintype "passive"))
    )
  )
)
